# Board_Schematic.net
KiCad netlist of a schematic drawn in EAGLE
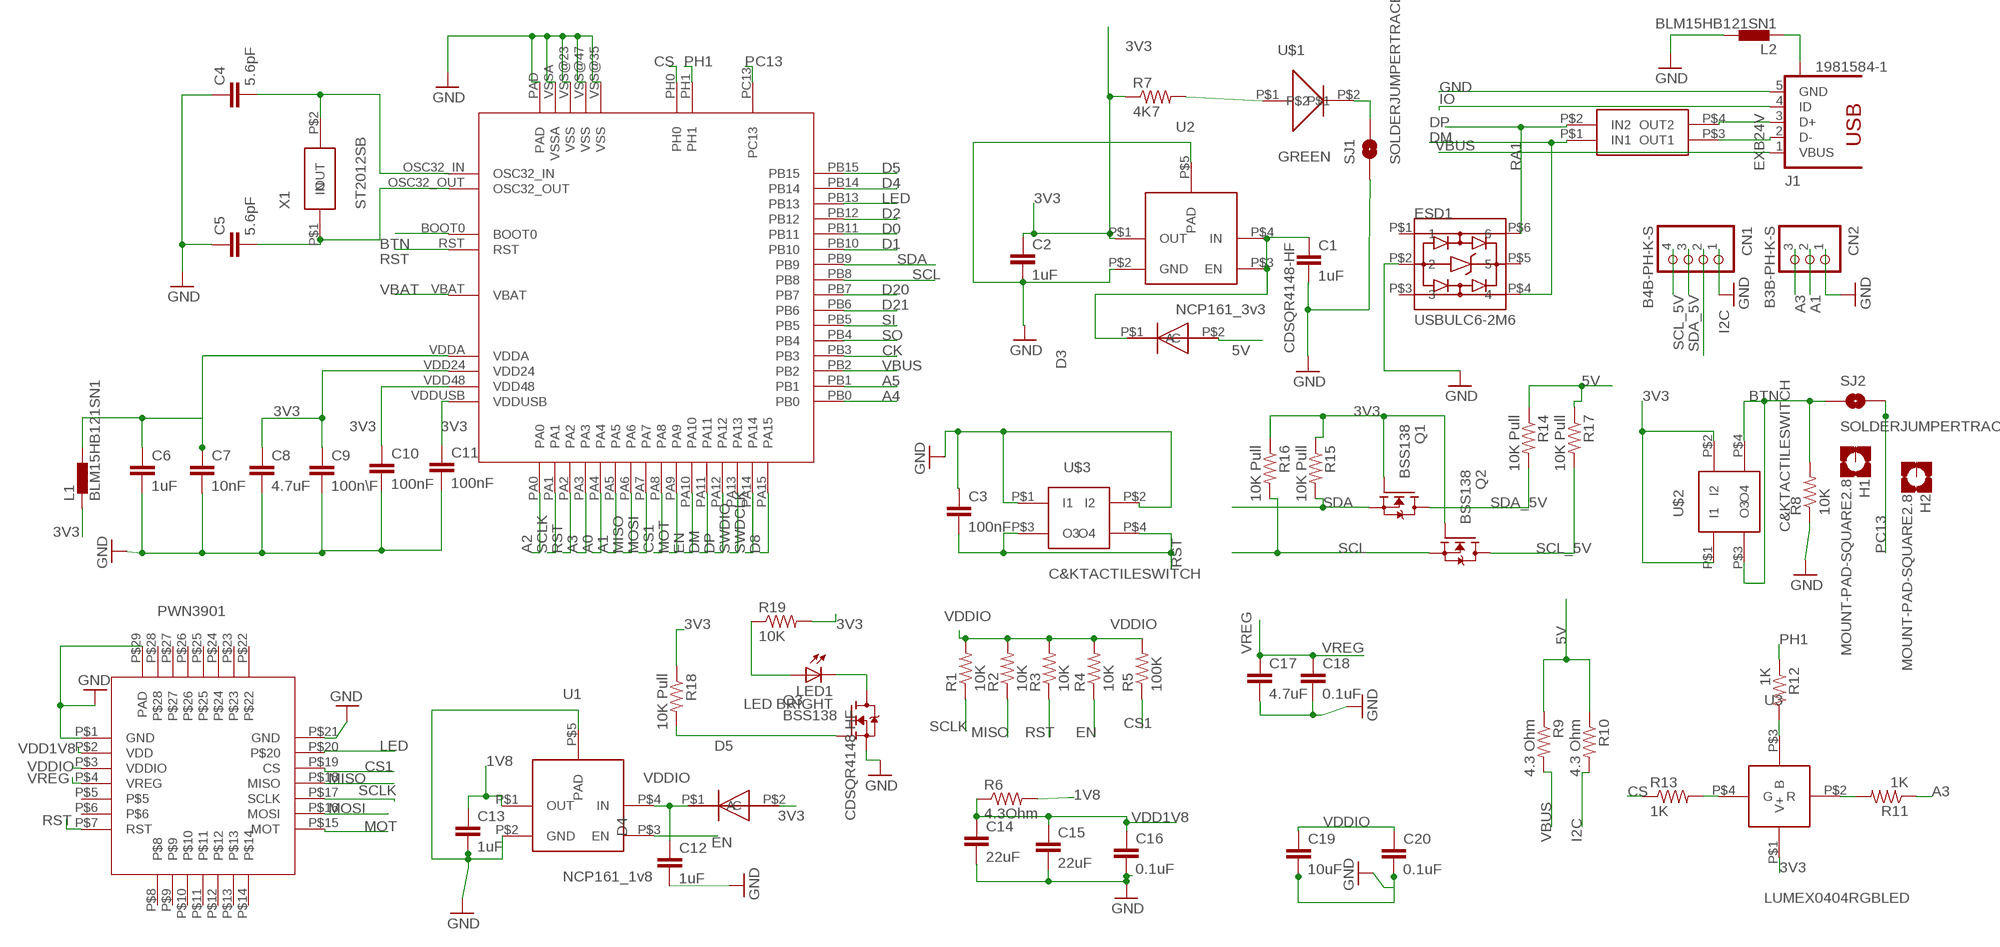
[diagram p0: schematic, sheet 1]

(export (version "E")
  (design (tool "Eeschema 10.0.6"))
  (components
    (comp (ref "C1")
      (value "1uF")
      (footprint "eagle-import:0402-CAP")
      (libsource (lib "eagle-import") (part "0402CAP.KW"))
    )
    (comp (ref "C2")
      (value "1uF")
      (footprint "eagle-import:0402-CAP")
      (libsource (lib "eagle-import") (part "0402CAP.KW"))
    )
    (comp (ref "C3")
      (value "100nF")
      (footprint "eagle-import:0402-CAP")
      (libsource (lib "eagle-import") (part "0402CAP.KW"))
    )
    (comp (ref "C4")
      (value "5.6pF")
      (footprint "eagle-import:0402-CAP")
      (libsource (lib "eagle-import") (part "0402CAP.KW"))
    )
    (comp (ref "C5")
      (value "5.6pF")
      (footprint "eagle-import:0402-CAP")
      (libsource (lib "eagle-import") (part "0402CAP.KW"))
    )
    (comp (ref "C6")
      (value "1uF")
      (footprint "eagle-import:0402-CAP")
      (libsource (lib "eagle-import") (part "0402CAP.KW"))
    )
    (comp (ref "C7")
      (value "10nF")
      (footprint "eagle-import:0402-CAP")
      (libsource (lib "eagle-import") (part "0402CAP.KW"))
    )
    (comp (ref "C8")
      (value "4.7uF")
      (footprint "eagle-import:0402-CAP")
      (libsource (lib "eagle-import") (part "0402CAP.KW"))
    )
    (comp (ref "C9")
      (value "100n\\F")
      (footprint "eagle-import:0402-CAP")
      (libsource (lib "eagle-import") (part "0402CAP.KW"))
    )
    (comp (ref "C10")
      (value "100nF")
      (footprint "eagle-import:0402-CAP")
      (libsource (lib "eagle-import") (part "0402CAP.KW"))
    )
    (comp (ref "C11")
      (value "100nF")
      (footprint "eagle-import:0402-CAP")
      (libsource (lib "eagle-import") (part "0402CAP.KW"))
    )
    (comp (ref "C12")
      (value "1uF")
      (footprint "eagle-import:0402-CAP")
      (libsource (lib "eagle-import") (part "0402CAP.KW"))
    )
    (comp (ref "C13")
      (value "1uF")
      (footprint "eagle-import:0402-CAP")
      (libsource (lib "eagle-import") (part "0402CAP.KW"))
    )
    (comp (ref "C14")
      (value "22uF")
      (footprint "eagle-import:0402-CAP")
      (libsource (lib "eagle-import") (part "0402CAP.KW"))
    )
    (comp (ref "C15")
      (value "22uF")
      (footprint "eagle-import:0402-CAP")
      (libsource (lib "eagle-import") (part "0402CAP.KW"))
    )
    (comp (ref "C16")
      (value "0.1uF")
      (footprint "eagle-import:0402-CAP")
      (libsource (lib "eagle-import") (part "0402CAP.KW"))
    )
    (comp (ref "C17")
      (value "4.7uF")
      (footprint "eagle-import:0402-CAP")
      (libsource (lib "eagle-import") (part "0402CAP.KW"))
    )
    (comp (ref "C18")
      (value "0.1uF")
      (footprint "eagle-import:0402-CAP")
      (libsource (lib "eagle-import") (part "0402CAP.KW"))
    )
    (comp (ref "C19")
      (value "10uF")
      (footprint "eagle-import:0402-CAP")
      (libsource (lib "eagle-import") (part "0402CAP.KW"))
    )
    (comp (ref "C20")
      (value "0.1uF")
      (footprint "eagle-import:0402-CAP")
      (libsource (lib "eagle-import") (part "0402CAP.KW"))
    )
    (comp (ref "CN1")
      (value "B4B-PH-K-S")
      (footprint "eagle-import:B4B-PH-K-S")
      (libsource (lib "eagle-import") (part "B4B-PH-K-S"))
    )
    (comp (ref "CN2")
      (value "B3B-PH-K-S")
      (footprint "eagle-import:B3B-PH-K-S")
      (libsource (lib "eagle-import") (part "B3B-PH-K-S"))
    )
    (comp (ref "D3")
      (value "CDSQR4148-HF")
      (footprint "eagle-import:CDSQR4148-HF")
      (libsource (lib "eagle-import") (part "CDSQR4148-HF"))
    )
    (comp (ref "D4")
      (value "CDSQR4148-HF")
      (footprint "eagle-import:CDSQR4148-HF")
      (libsource (lib "eagle-import") (part "CDSQR4148-HF"))
    )
    (comp (ref "ESD1")
      (value "USBULC6-2M6")
      (footprint "eagle-import:UQFN6")
      (libsource (lib "eagle-import") (part "USBULC6-2M6"))
    )
    (comp (ref "H1")
      (value "MOUNT-PAD-SQUARE2.8")
      (footprint "eagle-import:2,8-PAD-SQUARE")
      (libsource (lib "eagle-import") (part "MOUNT-PAD-SQUARE2.8"))
    )
    (comp (ref "H2")
      (value "MOUNT-PAD-SQUARE2.8")
      (footprint "eagle-import:2,8-PAD-SQUARE")
      (libsource (lib "eagle-import") (part "MOUNT-PAD-SQUARE2.8"))
    )
    (comp (ref "J1")
      (value "1981584-1")
      (footprint "eagle-import:1981584-1")
      (libsource (lib "eagle-import") (part "1981584-1"))
    )
    (comp (ref "L1")
      (value "BLM15HB121SN1")
      (footprint "eagle-import:0402")
      (libsource (lib "eagle-import") (part "BLM15HB121SN1"))
    )
    (comp (ref "L2")
      (value "BLM15HB121SN1")
      (footprint "eagle-import:0402")
      (libsource (lib "eagle-import") (part "BLM15HB121SN1"))
    )
    (comp (ref "LED1")
      (value "LED BRIGHT")
      (footprint "eagle-import:LM561C")
      (libsource (lib "eagle-import") (part "LED"))
    )
    (comp (ref "PWN3901")
      (value "COB_PMW3901")
      (footprint "eagle-import:COB")
      (libsource (lib "eagle-import") (part "COB_PMW3901"))
    )
    (comp (ref "Q1")
      (value "BSS138")
      (footprint "eagle-import:SOT23")
      (fields (field (name "MF") "Fairchild"))
      (libsource (lib "eagle-import") (part "BSS138"))
    )
    (comp (ref "Q2")
      (value "BSS138")
      (footprint "eagle-import:SOT23")
      (fields (field (name "MF") "Fairchild"))
      (libsource (lib "eagle-import") (part "BSS138"))
    )
    (comp (ref "Q3")
      (value "BSS138")
      (footprint "eagle-import:SOT23")
      (fields (field (name "MF") "Fairchild"))
      (libsource (lib "eagle-import") (part "BSS138"))
    )
    (comp (ref "R1")
      (value "10K")
      (footprint "eagle-import:0402-RES")
      (libsource (lib "eagle-import") (part "ladybug_0402RES.KW"))
    )
    (comp (ref "R2")
      (value "10K")
      (footprint "eagle-import:0402-RES")
      (libsource (lib "eagle-import") (part "ladybug_0402RES.KW"))
    )
    (comp (ref "R3")
      (value "10K")
      (footprint "eagle-import:0402-RES")
      (libsource (lib "eagle-import") (part "ladybug_0402RES.KW"))
    )
    (comp (ref "R4")
      (value "10K")
      (footprint "eagle-import:0402-RES")
      (libsource (lib "eagle-import") (part "ladybug_0402RES.KW"))
    )
    (comp (ref "R5")
      (value "100K")
      (footprint "eagle-import:0402-RES")
      (libsource (lib "eagle-import") (part "ladybug_0402RES.KW"))
    )
    (comp (ref "R6")
      (value "4.3Ohm")
      (footprint "eagle-import:0402-RES")
      (libsource (lib "eagle-import") (part "ladybug_0402RES.KW"))
    )
    (comp (ref "R7")
      (value "4K7")
      (footprint "eagle-import:0402-RES")
      (libsource (lib "eagle-import") (part "ladybug_0402RES.KW"))
    )
    (comp (ref "R8")
      (value "10K")
      (footprint "eagle-import:0402-RES")
      (libsource (lib "eagle-import") (part "ladybug_0402RES.KW"))
    )
    (comp (ref "R9")
      (value "4.3 Ohm")
      (footprint "eagle-import:0402-RES")
      (libsource (lib "eagle-import") (part "ladybug_0402RES.KW"))
    )
    (comp (ref "R10")
      (value "4.3 Ohm")
      (footprint "eagle-import:0402-RES")
      (libsource (lib "eagle-import") (part "ladybug_0402RES.KW"))
    )
    (comp (ref "R11")
      (value "1K")
      (footprint "eagle-import:0402-RES")
      (libsource (lib "eagle-import") (part "0402RES.KW"))
    )
    (comp (ref "R12")
      (value "1K")
      (footprint "eagle-import:0402-RES")
      (libsource (lib "eagle-import") (part "0402RES.KW"))
    )
    (comp (ref "R13")
      (value "1K")
      (footprint "eagle-import:0402-RES")
      (libsource (lib "eagle-import") (part "0402RES.KW"))
    )
    (comp (ref "R14")
      (value "10K Pull")
      (footprint "eagle-import:0402-RES")
      (libsource (lib "eagle-import") (part "ladybug_0402RES.KW"))
    )
    (comp (ref "R15")
      (value "10K Pull")
      (footprint "eagle-import:0402-RES")
      (libsource (lib "eagle-import") (part "ladybug_0402RES.KW"))
    )
    (comp (ref "R16")
      (value "10K Pull")
      (footprint "eagle-import:0402-RES")
      (libsource (lib "eagle-import") (part "ladybug_0402RES.KW"))
    )
    (comp (ref "R17")
      (value "10K Pull")
      (footprint "eagle-import:0402-RES")
      (libsource (lib "eagle-import") (part "ladybug_0402RES.KW"))
    )
    (comp (ref "R18")
      (value "10K Pull")
      (footprint "eagle-import:0402-RES")
      (libsource (lib "eagle-import") (part "ladybug_0402RES.KW"))
    )
    (comp (ref "R19")
      (value "10K")
      (footprint "eagle-import:0402-RES")
      (libsource (lib "eagle-import") (part "ladybug_0402RES.KW"))
    )
    (comp (ref "RA1")
      (value "EXB24V")
      (footprint "eagle-import:EXB24V")
      (libsource (lib "eagle-import") (part "EXB24V"))
    )
    (comp (ref "SJ1")
      (value "SOLDERJUMPERTRACE")
      (footprint "eagle-import:SJ_2S-TRACE")
      (libsource (lib "eagle-import") (part "SOLDERJUMPERTRACE"))
    )
    (comp (ref "SJ2")
      (value "SOLDERJUMPERTRACE")
      (footprint "eagle-import:SJ_2S-TRACE")
      (libsource (lib "eagle-import") (part "SOLDERJUMPERTRACE"))
    )
    (comp (ref "U$1")
      (value "GREEN")
      (footprint "eagle-import:0402LED")
      (libsource (lib "eagle-import") (part "0402LED"))
    )
    (comp (ref "U$2")
      (value "C&KTACTILESWITCH")
      (footprint "eagle-import:C&KTACTILESWITCH")
      (libsource (lib "eagle-import") (part "C&KTACTILESWITCH"))
    )
    (comp (ref "U$3")
      (value "C&KTACTILESWITCH")
      (footprint "eagle-import:C&KTACTILESWITCH")
      (libsource (lib "eagle-import") (part "C&KTACTILESWITCH"))
    )
    (comp (ref "U$4")
      (value "STM32L433")
      (footprint "eagle-import:QFN50P700X700X60-49N")
      (libsource (lib "eagle-import") (part "STM32L433"))
    )
    (comp (ref "U1")
      (value "NCP161_1v8")
      (footprint "eagle-import:NCP161")
      (libsource (lib "eagle-import") (part "NCP161"))
    )
    (comp (ref "U2")
      (value "NCP161_3v3")
      (footprint "eagle-import:NCP161")
      (libsource (lib "eagle-import") (part "NCP161"))
    )
    (comp (ref "U3")
      (value "LUMEX0404RGBLED")
      (footprint "eagle-import:LX0404")
      (libsource (lib "eagle-import") (part "LUMEX0404RGBLED"))
    )
    (comp (ref "X1")
      (value "ST2012SB")
      (footprint "eagle-import:ST2012SB")
      (libsource (lib "eagle-import") (part "ST2012SB"))
    )
  )
  (nets
    (net (code "1") (name "/1V8") (class "Default")
      (node (ref "C13") (pin "1") (pinfunction "1_1") (pintype "passive"))
      (node (ref "R6") (pin "2") (pinfunction "2_2") (pintype "passive"))
      (node (ref "U1") (pin "P$1") (pinfunction "OUT_P$1") (pintype "power_in"))
    )
    (net (code "2") (name "/3V3") (class "Default")
      (node (ref "C10") (pin "1") (pinfunction "1_1") (pintype "passive"))
      (node (ref "C11") (pin "1") (pinfunction "1_1") (pintype "passive"))
      (node (ref "C2") (pin "1") (pinfunction "1_1") (pintype "passive"))
      (node (ref "C8") (pin "1") (pinfunction "1_1") (pintype "passive"))
      (node (ref "C9") (pin "1") (pinfunction "1_1") (pintype "passive"))
      (node (ref "D4") (pin "P$2") (pinfunction "A_P$2") (pintype "bidirectional"))
      (node (ref "L1") (pin "1") (pinfunction "1_1") (pintype "passive"))
      (node (ref "Q1") (pin "1") (pinfunction "G_1") (pintype "passive"))
      (node (ref "Q2") (pin "1") (pinfunction "G_1") (pintype "passive"))
      (node (ref "R15") (pin "1") (pinfunction "1_1") (pintype "passive"))
      (node (ref "R16") (pin "1") (pinfunction "1_1") (pintype "passive"))
      (node (ref "R18") (pin "1") (pinfunction "1_1") (pintype "passive"))
      (node (ref "R19") (pin "2") (pinfunction "2_2") (pintype "passive"))
      (node (ref "R7") (pin "1") (pinfunction "1_1") (pintype "passive"))
      (node (ref "U$2") (pin "P$1") (pinfunction "I1_P$1") (pintype "bidirectional"))
      (node (ref "U$2") (pin "P$2") (pinfunction "I2_P$2") (pintype "bidirectional"))
      (node (ref "U$4") (pin "VDD24") (pinfunction "VDD24_VDD24") (pintype "bidirectional"))
      (node (ref "U$4") (pin "VDD48") (pinfunction "VDD48_VDD48") (pintype "bidirectional"))
      (node (ref "U$4") (pin "VDDUSB") (pinfunction "VDDUSB_VDDUSB") (pintype "bidirectional"))
      (node (ref "U2") (pin "P$1") (pinfunction "OUT_P$1") (pintype "power_in"))
      (node (ref "U3") (pin "P$1") (pinfunction "V+_P$1") (pintype "bidirectional"))
    )
    (net (code "3") (name "/5V") (class "Default")
      (node (ref "D3") (pin "P$2") (pinfunction "A_P$2") (pintype "bidirectional"))
      (node (ref "R10") (pin "1") (pinfunction "1_1") (pintype "passive"))
      (node (ref "R14") (pin "1") (pinfunction "1_1") (pintype "passive"))
      (node (ref "R17") (pin "1") (pinfunction "1_1") (pintype "passive"))
      (node (ref "R9") (pin "1") (pinfunction "1_1") (pintype "passive"))
    )
    (net (code "4") (name "/A0") (class "Default")
      (node (ref "U$4") (pin "PA4") (pinfunction "PA4_PA4") (pintype "bidirectional"))
    )
    (net (code "5") (name "/A1") (class "Default")
      (node (ref "CN2") (pin "2") (pinfunction "2_2") (pintype "passive"))
      (node (ref "U$4") (pin "PA5") (pinfunction "PA5_PA5") (pintype "bidirectional"))
    )
    (net (code "6") (name "/A2") (class "Default")
      (node (ref "U$4") (pin "PA0") (pinfunction "PA0_PA0") (pintype "bidirectional"))
    )
    (net (code "7") (name "/A3") (class "Default")
      (node (ref "CN2") (pin "3") (pinfunction "3_3") (pintype "passive"))
      (node (ref "R11") (pin "1") (pinfunction "1_1") (pintype "passive"))
      (node (ref "U$4") (pin "PA3") (pinfunction "PA3_PA3") (pintype "bidirectional"))
    )
    (net (code "8") (name "/A4") (class "Default")
      (node (ref "U$4") (pin "PB0") (pinfunction "PB0_PB0") (pintype "bidirectional"))
    )
    (net (code "9") (name "/A5") (class "Default")
      (node (ref "U$4") (pin "PB1") (pinfunction "PB1_PB1") (pintype "bidirectional"))
    )
    (net (code "10") (name "/BTN") (class "Default")
      (node (ref "R8") (pin "2") (pinfunction "2_2") (pintype "passive"))
      (node (ref "SJ2") (pin "1") (pinfunction "1_1") (pintype "passive"))
      (node (ref "U$2") (pin "P$3") (pinfunction "O3_P$3") (pintype "bidirectional"))
      (node (ref "U$2") (pin "P$4") (pinfunction "O4_P$4") (pintype "bidirectional"))
      (node (ref "U$4") (pin "BOOT0") (pinfunction "BOOT0_BOOT0") (pintype "bidirectional"))
    )
    (net (code "11") (name "/CK") (class "Default")
      (node (ref "U$4") (pin "PB3") (pinfunction "PB3_PB3") (pintype "bidirectional"))
    )
    (net (code "12") (name "/CS") (class "Default")
      (node (ref "R13") (pin "1") (pinfunction "1_1") (pintype "passive"))
      (node (ref "U$4") (pin "PH0") (pinfunction "PH0_PH0") (pintype "bidirectional"))
    )
    (net (code "13") (name "/CS1") (class "Default")
      (node (ref "PWN3901") (pin "P$19") (pinfunction "CS_P$19") (pintype "bidirectional"))
      (node (ref "R5") (pin "1") (pinfunction "1_1") (pintype "passive"))
      (node (ref "U$4") (pin "PA8") (pinfunction "PA8_PA8") (pintype "bidirectional"))
    )
    (net (code "14") (name "/D0") (class "Default")
      (node (ref "U$4") (pin "PB11") (pinfunction "PB11_PB11") (pintype "bidirectional"))
    )
    (net (code "15") (name "/D1") (class "Default")
      (node (ref "U$4") (pin "PB10") (pinfunction "PB10_PB10") (pintype "bidirectional"))
    )
    (net (code "16") (name "/D2") (class "Default")
      (node (ref "U$4") (pin "PB12") (pinfunction "PB12_PB12") (pintype "bidirectional"))
    )
    (net (code "17") (name "/D4") (class "Default")
      (node (ref "U$4") (pin "PB14") (pinfunction "PB14_PB14") (pintype "bidirectional"))
    )
    (net (code "18") (name "/D5") (class "Default")
      (node (ref "Q3") (pin "1") (pinfunction "G_1") (pintype "passive"))
      (node (ref "R18") (pin "2") (pinfunction "2_2") (pintype "passive"))
      (node (ref "U$4") (pin "PB15") (pinfunction "PB15_PB15") (pintype "bidirectional"))
    )
    (net (code "19") (name "/D8") (class "Default")
      (node (ref "U$4") (pin "PA15") (pinfunction "PA15_PA15") (pintype "bidirectional"))
    )
    (net (code "20") (name "/D20") (class "Default")
      (node (ref "U$4") (pin "PB7") (pinfunction "PB7_PB7") (pintype "bidirectional"))
    )
    (net (code "21") (name "/D21") (class "Default")
      (node (ref "U$4") (pin "PB6") (pinfunction "PB6_PB6") (pintype "bidirectional"))
    )
    (net (code "22") (name "/DM") (class "Default")
      (node (ref "ESD1") (pin "P$4") (pinfunction "4_P$4") (pintype "bidirectional"))
      (node (ref "RA1") (pin "P$1") (pinfunction "IN1_P$1") (pintype "bidirectional"))
      (node (ref "U$4") (pin "PA11") (pinfunction "PA11_PA11") (pintype "bidirectional"))
    )
    (net (code "23") (name "/DP") (class "Default")
      (node (ref "ESD1") (pin "P$6") (pinfunction "6_P$6") (pintype "bidirectional"))
      (node (ref "RA1") (pin "P$2") (pinfunction "IN2_P$2") (pintype "bidirectional"))
      (node (ref "U$4") (pin "PA12") (pinfunction "PA12_PA12") (pintype "bidirectional"))
    )
    (net (code "24") (name "/EN") (class "Default")
      (node (ref "R4") (pin "1") (pinfunction "1_1") (pintype "passive"))
      (node (ref "U$4") (pin "PA10") (pinfunction "PA10_PA10") (pintype "bidirectional"))
      (node (ref "U1") (pin "P$3") (pinfunction "EN_P$3") (pintype "bidirectional"))
    )
    (net (code "25") (name "/I2C") (class "Default")
      (node (ref "CN1") (pin "2") (pinfunction "2_2") (pintype "passive"))
      (node (ref "R10") (pin "2") (pinfunction "2_2") (pintype "passive"))
    )
    (net (code "26") (name "/IO") (class "Default")
      (node (ref "J1") (pin "4") (pinfunction "ID_4") (pintype "passive"))
    )
    (net (code "27") (name "/LED") (class "Default")
      (node (ref "PWN3901") (pin "P$20") (pinfunction "P$20_P$20") (pintype "bidirectional"))
      (node (ref "U$4") (pin "PB13") (pinfunction "PB13_PB13") (pintype "bidirectional"))
    )
    (net (code "28") (name "/MISO") (class "Default")
      (node (ref "PWN3901") (pin "P$18") (pinfunction "MISO_P$18") (pintype "bidirectional"))
      (node (ref "R2") (pin "1") (pinfunction "1_1") (pintype "passive"))
      (node (ref "U$4") (pin "PA6") (pinfunction "PA6_PA6") (pintype "bidirectional"))
    )
    (net (code "29") (name "/MOSI") (class "Default")
      (node (ref "PWN3901") (pin "P$16") (pinfunction "MOSI_P$16") (pintype "bidirectional"))
      (node (ref "U$4") (pin "PA7") (pinfunction "PA7_PA7") (pintype "bidirectional"))
    )
    (net (code "30") (name "/MOT") (class "Default")
      (node (ref "PWN3901") (pin "P$15") (pinfunction "MOT_P$15") (pintype "bidirectional"))
      (node (ref "U$4") (pin "PA9") (pinfunction "PA9_PA9") (pintype "bidirectional"))
    )
    (net (code "31") (name "/PC13") (class "Default")
      (node (ref "SJ2") (pin "2") (pinfunction "2_2") (pintype "passive"))
      (node (ref "U$4") (pin "PC13") (pinfunction "PC13_PC13") (pintype "bidirectional"))
    )
    (net (code "32") (name "/PH1") (class "Default")
      (node (ref "R12") (pin "1") (pinfunction "1_1") (pintype "passive"))
      (node (ref "U$4") (pin "PH1") (pinfunction "PH1_PH1") (pintype "bidirectional"))
    )
    (net (code "33") (name "/RST") (class "Default")
      (node (ref "C3") (pin "2") (pinfunction "2_2") (pintype "passive"))
      (node (ref "PWN3901") (pin "P$7") (pinfunction "RST_P$7") (pintype "bidirectional"))
      (node (ref "R3") (pin "1") (pinfunction "1_1") (pintype "passive"))
      (node (ref "U$3") (pin "P$3") (pinfunction "O3_P$3") (pintype "bidirectional"))
      (node (ref "U$3") (pin "P$4") (pinfunction "O4_P$4") (pintype "bidirectional"))
      (node (ref "U$4") (pin "PA2") (pinfunction "PA2_PA2") (pintype "bidirectional"))
      (node (ref "U$4") (pin "RST") (pinfunction "RST_RST") (pintype "bidirectional"))
    )
    (net (code "34") (name "/SCL") (class "Default")
      (node (ref "Q2") (pin "2") (pinfunction "S_2") (pintype "passive"))
      (node (ref "R16") (pin "2") (pinfunction "2_2") (pintype "passive"))
      (node (ref "U$4") (pin "PB8") (pinfunction "PB8_PB8") (pintype "bidirectional"))
    )
    (net (code "35") (name "/SCLK") (class "Default")
      (node (ref "PWN3901") (pin "P$17") (pinfunction "SCLK_P$17") (pintype "bidirectional"))
      (node (ref "R1") (pin "1") (pinfunction "1_1") (pintype "passive"))
      (node (ref "U$4") (pin "PA1") (pinfunction "PA1_PA1") (pintype "bidirectional"))
    )
    (net (code "36") (name "/SCL_5V") (class "Default")
      (node (ref "CN1") (pin "4") (pinfunction "4_4") (pintype "passive"))
      (node (ref "Q2") (pin "3") (pinfunction "D_3") (pintype "passive"))
      (node (ref "R17") (pin "2") (pinfunction "2_2") (pintype "passive"))
    )
    (net (code "37") (name "/SDA") (class "Default")
      (node (ref "Q1") (pin "2") (pinfunction "S_2") (pintype "passive"))
      (node (ref "R15") (pin "2") (pinfunction "2_2") (pintype "passive"))
      (node (ref "U$4") (pin "PB9") (pinfunction "PB9_PB9") (pintype "bidirectional"))
    )
    (net (code "38") (name "/SDA_5V") (class "Default")
      (node (ref "CN1") (pin "3") (pinfunction "3_3") (pintype "passive"))
      (node (ref "Q1") (pin "3") (pinfunction "D_3") (pintype "passive"))
      (node (ref "R14") (pin "2") (pinfunction "2_2") (pintype "passive"))
    )
    (net (code "39") (name "/SI") (class "Default")
      (node (ref "U$4") (pin "PB5") (pinfunction "PB5_PB5") (pintype "bidirectional"))
    )
    (net (code "40") (name "/SO") (class "Default")
      (node (ref "U$4") (pin "PB4") (pinfunction "PB4_PB4") (pintype "bidirectional"))
    )
    (net (code "41") (name "/SWDCLK") (class "Default")
      (node (ref "U$4") (pin "PA14") (pinfunction "PA14_PA14") (pintype "bidirectional"))
    )
    (net (code "42") (name "/SWDIO") (class "Default")
      (node (ref "U$4") (pin "PA13") (pinfunction "PA13_PA13") (pintype "bidirectional"))
    )
    (net (code "43") (name "/VBAT") (class "Default")
      (node (ref "U$4") (pin "VBAT") (pinfunction "VBAT_VBAT") (pintype "bidirectional"))
    )
    (net (code "44") (name "/VBUS") (class "Default")
      (node (ref "J1") (pin "1") (pinfunction "VBUS_1") (pintype "passive"))
      (node (ref "R9") (pin "2") (pinfunction "2_2") (pintype "passive"))
      (node (ref "U$4") (pin "PB2") (pinfunction "PB2_PB2") (pintype "bidirectional"))
    )
    (net (code "45") (name "/VDD1V8") (class "Default")
      (node (ref "C14") (pin "1") (pinfunction "1_1") (pintype "passive"))
      (node (ref "C15") (pin "1") (pinfunction "1_1") (pintype "passive"))
      (node (ref "C16") (pin "1") (pinfunction "1_1") (pintype "passive"))
      (node (ref "PWN3901") (pin "P$2") (pinfunction "VDD_P$2") (pintype "bidirectional"))
      (node (ref "R6") (pin "1") (pinfunction "1_1") (pintype "passive"))
    )
    (net (code "46") (name "/VDDIO") (class "Default")
      (node (ref "C12") (pin "1") (pinfunction "1_1") (pintype "passive"))
      (node (ref "C19") (pin "1") (pinfunction "1_1") (pintype "passive"))
      (node (ref "C20") (pin "1") (pinfunction "1_1") (pintype "passive"))
      (node (ref "D4") (pin "P$1") (pinfunction "C_P$1") (pintype "bidirectional"))
      (node (ref "PWN3901") (pin "P$3") (pinfunction "VDDIO_P$3") (pintype "bidirectional"))
      (node (ref "R1") (pin "2") (pinfunction "2_2") (pintype "passive"))
      (node (ref "R2") (pin "2") (pinfunction "2_2") (pintype "passive"))
      (node (ref "R3") (pin "2") (pinfunction "2_2") (pintype "passive"))
      (node (ref "R4") (pin "2") (pinfunction "2_2") (pintype "passive"))
      (node (ref "R5") (pin "2") (pinfunction "2_2") (pintype "passive"))
      (node (ref "U1") (pin "P$4") (pinfunction "IN_P$4") (pintype "power_in"))
    )
    (net (code "47") (name "/VREG") (class "Default")
      (node (ref "C17") (pin "1") (pinfunction "1_1") (pintype "passive"))
      (node (ref "C18") (pin "1") (pinfunction "1_1") (pintype "passive"))
      (node (ref "PWN3901") (pin "P$4") (pinfunction "VREG_P$4") (pintype "bidirectional"))
    )
    (net (code "48") (name "GND") (class "Default")
      (node (ref "C1") (pin "2") (pinfunction "2_2") (pintype "passive"))
      (node (ref "C10") (pin "2") (pinfunction "2_2") (pintype "passive"))
      (node (ref "C11") (pin "2") (pinfunction "2_2") (pintype "passive"))
      (node (ref "C12") (pin "2") (pinfunction "2_2") (pintype "passive"))
      (node (ref "C13") (pin "2") (pinfunction "2_2") (pintype "passive"))
      (node (ref "C14") (pin "2") (pinfunction "2_2") (pintype "passive"))
      (node (ref "C15") (pin "2") (pinfunction "2_2") (pintype "passive"))
      (node (ref "C16") (pin "2") (pinfunction "2_2") (pintype "passive"))
      (node (ref "C17") (pin "2") (pinfunction "2_2") (pintype "passive"))
      (node (ref "C18") (pin "2") (pinfunction "2_2") (pintype "passive"))
      (node (ref "C19") (pin "2") (pinfunction "2_2") (pintype "passive"))
      (node (ref "C2") (pin "2") (pinfunction "2_2") (pintype "passive"))
      (node (ref "C20") (pin "2") (pinfunction "2_2") (pintype "passive"))
      (node (ref "C3") (pin "1") (pinfunction "1_1") (pintype "passive"))
      (node (ref "C4") (pin "1") (pinfunction "1_1") (pintype "passive"))
      (node (ref "C5") (pin "1") (pinfunction "1_1") (pintype "passive"))
      (node (ref "C6") (pin "2") (pinfunction "2_2") (pintype "passive"))
      (node (ref "C7") (pin "2") (pinfunction "2_2") (pintype "passive"))
      (node (ref "C8") (pin "2") (pinfunction "2_2") (pintype "passive"))
      (node (ref "C9") (pin "2") (pinfunction "2_2") (pintype "passive"))
      (node (ref "CN1") (pin "1") (pinfunction "1_1") (pintype "passive"))
      (node (ref "CN2") (pin "1") (pinfunction "1_1") (pintype "passive"))
      (node (ref "ESD1") (pin "P$2") (pinfunction "2_P$2") (pintype "bidirectional"))
      (node (ref "J1") (pin "5") (pinfunction "GND_5") (pintype "passive"))
      (node (ref "L2") (pin "2") (pinfunction "2_2") (pintype "passive"))
      (node (ref "PWN3901") (pin "P$1") (pinfunction "GND_P$1") (pintype "bidirectional"))
      (node (ref "PWN3901") (pin "P$21") (pinfunction "GND_P$21") (pintype "bidirectional"))
      (node (ref "PWN3901") (pin "P$29") (pinfunction "PAD_P$29") (pintype "bidirectional"))
      (node (ref "Q3") (pin "2") (pinfunction "S_2") (pintype "passive"))
      (node (ref "R8") (pin "1") (pinfunction "1_1") (pintype "passive"))
      (node (ref "SJ1") (pin "1") (pinfunction "1_1") (pintype "passive"))
      (node (ref "U$3") (pin "P$1") (pinfunction "I1_P$1") (pintype "bidirectional"))
      (node (ref "U$3") (pin "P$2") (pinfunction "I2_P$2") (pintype "bidirectional"))
      (node (ref "U$4") (pin "PAD") (pinfunction "PAD_PAD") (pintype "bidirectional"))
      (node (ref "U$4") (pin "VSS@23") (pinfunction "VSS_VSS@23") (pintype "bidirectional"))
      (node (ref "U$4") (pin "VSS@35") (pinfunction "VSS_VSS@35") (pintype "bidirectional"))
      (node (ref "U$4") (pin "VSS@47") (pinfunction "VSS_VSS@47") (pintype "bidirectional"))
      (node (ref "U$4") (pin "VSSA") (pinfunction "VSSA_VSSA") (pintype "bidirectional"))
      (node (ref "U1") (pin "P$2") (pinfunction "GND_P$2") (pintype "power_in"))
      (node (ref "U1") (pin "P$5") (pinfunction "PAD_P$5") (pintype "power_in"))
      (node (ref "U2") (pin "P$2") (pinfunction "GND_P$2") (pintype "power_in"))
      (node (ref "U2") (pin "P$5") (pinfunction "PAD_P$5") (pintype "power_in"))
    )
    (net (code "49") (name "Net-(C6-Pad1)") (class "Default")
      (node (ref "C6") (pin "1") (pinfunction "1_1") (pintype "passive"))
      (node (ref "C7") (pin "1") (pinfunction "1_1") (pintype "passive"))
      (node (ref "L1") (pin "2") (pinfunction "2_2") (pintype "passive"))
      (node (ref "U$4") (pin "VDDA") (pinfunction "VDDA_VDDA") (pintype "bidirectional"))
    )
    (net (code "50") (name "Net-(D3-C)") (class "Default")
      (node (ref "C1") (pin "1") (pinfunction "1_1") (pintype "passive"))
      (node (ref "D3") (pin "P$1") (pinfunction "C_P$1") (pintype "bidirectional"))
      (node (ref "U2") (pin "P$3") (pinfunction "EN_P$3") (pintype "bidirectional"))
      (node (ref "U2") (pin "P$4") (pinfunction "IN_P$4") (pintype "power_in"))
    )
    (net (code "51") (name "Net-(J1-D+)") (class "Default")
      (node (ref "J1") (pin "3") (pinfunction "D+_3") (pintype "passive"))
      (node (ref "RA1") (pin "P$4") (pinfunction "OUT2_P$4") (pintype "bidirectional"))
    )
    (net (code "52") (name "Net-(J1-D-)") (class "Default")
      (node (ref "J1") (pin "2") (pinfunction "D-_2") (pintype "passive"))
      (node (ref "RA1") (pin "P$3") (pinfunction "OUT1_P$3") (pintype "bidirectional"))
    )
    (net (code "53") (name "Net-(J1-PadS1)") (class "Default")
      (node (ref "J1") (pin "S1") (pinfunction "S1_S1") (pintype "passive"))
      (node (ref "L2") (pin "1") (pinfunction "1_1") (pintype "passive"))
    )
    (net (code "54") (name "Net-(LED1-A-PadA1)") (class "Default")
      (node (ref "LED1") (pin "A1") (pinfunction "A_A1") (pintype "passive"))
      (node (ref "LED1") (pin "A2") (pinfunction "A_A2") (pintype "passive"))
      (node (ref "LED1") (pin "A3") (pinfunction "A_A3") (pintype "passive"))
      (node (ref "R19") (pin "1") (pinfunction "1_1") (pintype "passive"))
    )
    (net (code "55") (name "Net-(Q3-D)") (class "Default")
      (node (ref "LED1") (pin "C1") (pinfunction "C_C1") (pintype "passive"))
      (node (ref "LED1") (pin "C2") (pinfunction "C_C2") (pintype "passive"))
      (node (ref "LED1") (pin "C3") (pinfunction "C_C3") (pintype "passive"))
      (node (ref "Q3") (pin "3") (pinfunction "D_3") (pintype "passive"))
    )
    (net (code "56") (name "Net-(R7-Pad2)") (class "Default")
      (node (ref "R7") (pin "2") (pinfunction "2_2") (pintype "passive"))
      (node (ref "U$1") (pin "P$1") (pinfunction "P$1_P$1") (pintype "bidirectional"))
    )
    (net (code "57") (name "Net-(SJ1-Pad2)") (class "Default")
      (node (ref "SJ1") (pin "2") (pinfunction "2_2") (pintype "passive"))
      (node (ref "U$1") (pin "P$2") (pinfunction "P$2_P$2") (pintype "bidirectional"))
    )
    (net (code "58") (name "Net-(U3-B)") (class "Default")
      (node (ref "R12") (pin "2") (pinfunction "2_2") (pintype "passive"))
      (node (ref "U3") (pin "P$3") (pinfunction "B_P$3") (pintype "bidirectional"))
    )
    (net (code "59") (name "Net-(U3-G)") (class "Default")
      (node (ref "R13") (pin "2") (pinfunction "2_2") (pintype "passive"))
      (node (ref "U3") (pin "P$4") (pinfunction "G_P$4") (pintype "bidirectional"))
    )
    (net (code "60") (name "Net-(U3-R)") (class "Default")
      (node (ref "R11") (pin "2") (pinfunction "2_2") (pintype "passive"))
      (node (ref "U3") (pin "P$2") (pinfunction "R_P$2") (pintype "bidirectional"))
    )
    (net (code "61") (name "Net-(X1-IN)") (class "Default")
      (node (ref "C5") (pin "2") (pinfunction "2_2") (pintype "passive"))
      (node (ref "U$4") (pin "OSC32_OUT") (pinfunction "OSC32_OUT_OSC32_OUT") (pintype "bidirectional"))
      (node (ref "X1") (pin "P$1") (pinfunction "IN_P$1") (pintype "bidirectional"))
    )
    (net (code "62") (name "Net-(X1-OUT)") (class "Default")
      (node (ref "C4") (pin "2") (pinfunction "2_2") (pintype "passive"))
      (node (ref "U$4") (pin "OSC32_IN") (pinfunction "OSC32_IN_OSC32_IN") (pintype "bidirectional"))
      (node (ref "X1") (pin "P$2") (pinfunction "OUT_P$2") (pintype "bidirectional"))
    )
    (net (code "63") (name "unconnected-(ESD1-1-PadP$1)") (class "Default")
      (node (ref "ESD1") (pin "P$1") (pinfunction "1_P$1") (pintype "bidirectional"))
    )
    (net (code "64") (name "unconnected-(ESD1-3-PadP$3)") (class "Default")
      (node (ref "ESD1") (pin "P$3") (pinfunction "3_P$3") (pintype "bidirectional"))
    )
    (net (code "65") (name "unconnected-(ESD1-5-PadP$5)") (class "Default")
      (node (ref "ESD1") (pin "P$5") (pinfunction "5_P$5") (pintype "bidirectional"))
    )
    (net (code "66") (name "unconnected-(H1-MOUNT-PadB2,8)") (class "Default")
      (node (ref "H1") (pin "B2,8") (pinfunction "MOUNT_B2,8") (pintype "passive"))
    )
    (net (code "67") (name "unconnected-(H2-MOUNT-PadB2,8)") (class "Default")
      (node (ref "H2") (pin "B2,8") (pinfunction "MOUNT_B2,8") (pintype "passive"))
    )
    (net (code "68") (name "unconnected-(PWN3901-PadP$5)") (class "Default")
      (node (ref "PWN3901") (pin "P$5") (pinfunction "P$5_P$5") (pintype "bidirectional"))
    )
    (net (code "69") (name "unconnected-(PWN3901-PadP$6)") (class "Default")
      (node (ref "PWN3901") (pin "P$6") (pinfunction "P$6_P$6") (pintype "bidirectional"))
    )
    (net (code "70") (name "unconnected-(PWN3901-PadP$8)") (class "Default")
      (node (ref "PWN3901") (pin "P$8") (pinfunction "P$8_P$8") (pintype "bidirectional"))
    )
    (net (code "71") (name "unconnected-(PWN3901-PadP$9)") (class "Default")
      (node (ref "PWN3901") (pin "P$9") (pinfunction "P$9_P$9") (pintype "bidirectional"))
    )
    (net (code "72") (name "unconnected-(PWN3901-PadP$10)") (class "Default")
      (node (ref "PWN3901") (pin "P$10") (pinfunction "P$10_P$10") (pintype "bidirectional"))
    )
    (net (code "73") (name "unconnected-(PWN3901-PadP$11)") (class "Default")
      (node (ref "PWN3901") (pin "P$11") (pinfunction "P$11_P$11") (pintype "bidirectional"))
    )
    (net (code "74") (name "unconnected-(PWN3901-PadP$12)") (class "Default")
      (node (ref "PWN3901") (pin "P$12") (pinfunction "P$12_P$12") (pintype "bidirectional"))
    )
    (net (code "75") (name "unconnected-(PWN3901-PadP$13)") (class "Default")
      (node (ref "PWN3901") (pin "P$13") (pinfunction "P$13_P$13") (pintype "bidirectional"))
    )
    (net (code "76") (name "unconnected-(PWN3901-PadP$14)") (class "Default")
      (node (ref "PWN3901") (pin "P$14") (pinfunction "P$14_P$14") (pintype "bidirectional"))
    )
    (net (code "77") (name "unconnected-(PWN3901-PadP$22)") (class "Default")
      (node (ref "PWN3901") (pin "P$22") (pinfunction "P$22_P$22") (pintype "bidirectional"))
    )
    (net (code "78") (name "unconnected-(PWN3901-PadP$23)") (class "Default")
      (node (ref "PWN3901") (pin "P$23") (pinfunction "P$23_P$23") (pintype "bidirectional"))
    )
    (net (code "79") (name "unconnected-(PWN3901-PadP$24)") (class "Default")
      (node (ref "PWN3901") (pin "P$24") (pinfunction "P$24_P$24") (pintype "bidirectional"))
    )
    (net (code "80") (name "unconnected-(PWN3901-PadP$25)") (class "Default")
      (node (ref "PWN3901") (pin "P$25") (pinfunction "P$25_P$25") (pintype "bidirectional"))
    )
    (net (code "81") (name "unconnected-(PWN3901-PadP$26)") (class "Default")
      (node (ref "PWN3901") (pin "P$26") (pinfunction "P$26_P$26") (pintype "bidirectional"))
    )
    (net (code "82") (name "unconnected-(PWN3901-PadP$27)") (class "Default")
      (node (ref "PWN3901") (pin "P$27") (pinfunction "P$27_P$27") (pintype "bidirectional"))
    )
    (net (code "83") (name "unconnected-(PWN3901-PadP$28)") (class "Default")
      (node (ref "PWN3901") (pin "P$28") (pinfunction "P$28_P$28") (pintype "bidirectional"))
    )
  )
)
